# CM108B.net
KiCad netlist of a schematic drawn in Altium Designer
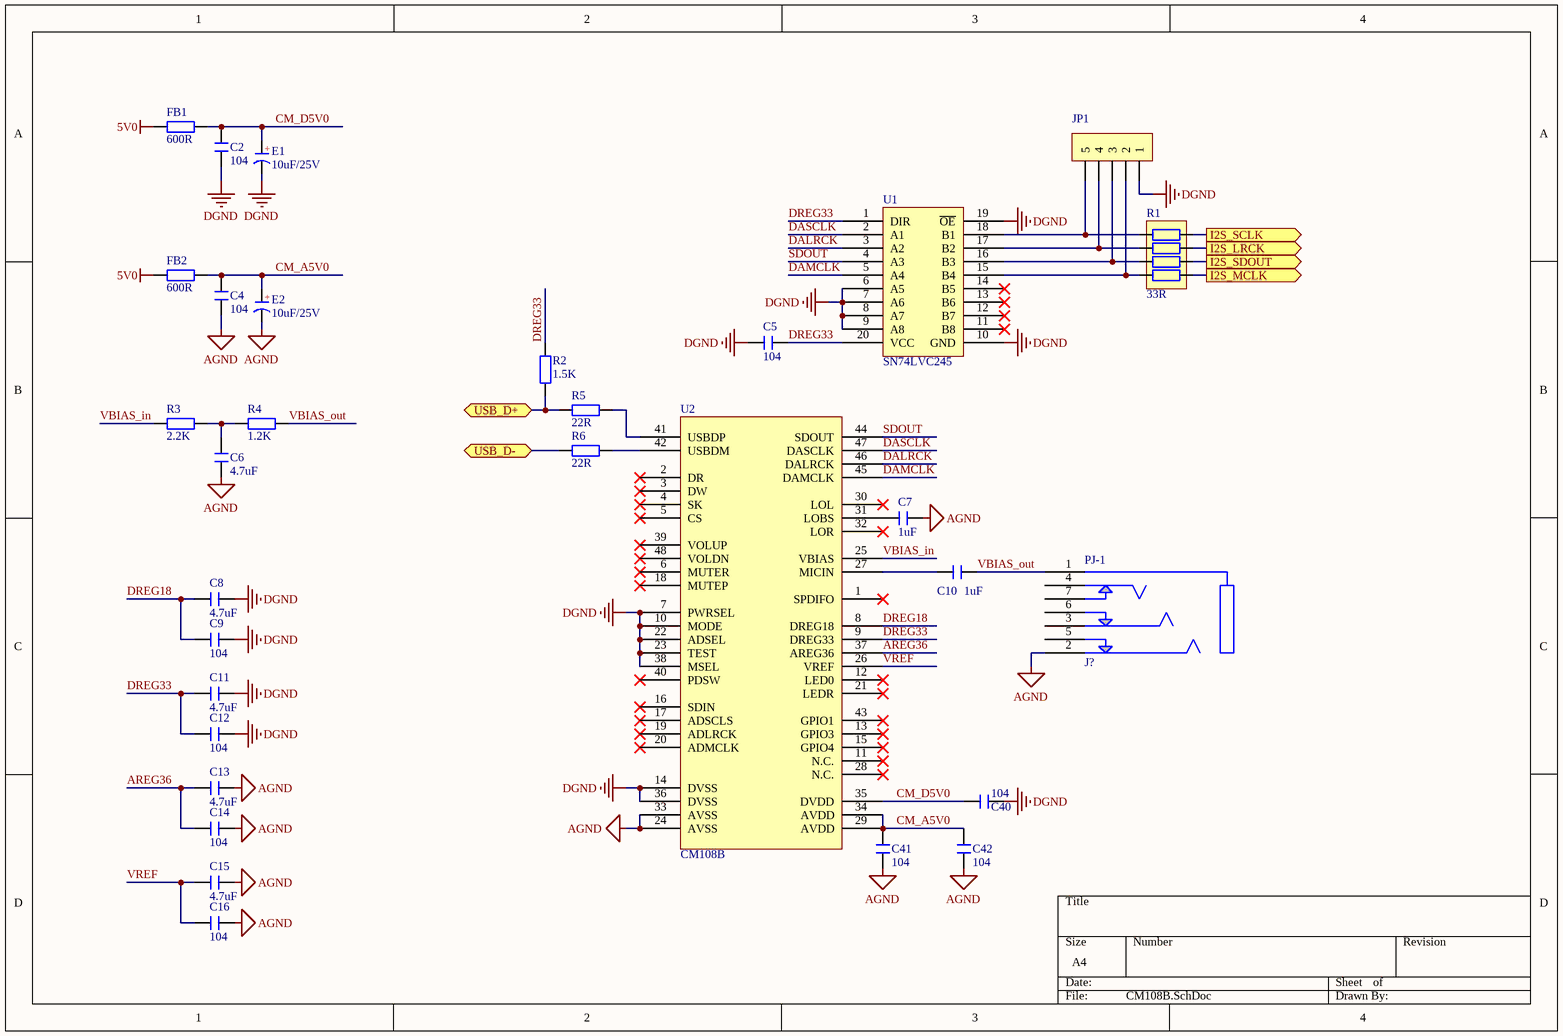
[diagram p0: CM108B.SchDoc]

(export (version "E")
  (design (tool "Eeschema 10.0.6"))
  (components
    (comp (ref "C2")
      (value "104")
      (footprint "C 0603_L")
      (description "贴片电容")
      (libsource (lib "0.1 - 电阻-电容-电感") (part "C"))
    )
    (comp (ref "C4")
      (value "104")
      (footprint "C 0603_L")
      (description "贴片电容")
      (libsource (lib "0.1 - 电阻-电容-电感") (part "C"))
    )
    (comp (ref "C5")
      (value "104")
      (footprint "C 0603_L")
      (description "贴片电容")
      (libsource (lib "0.1 - 电阻-电容-电感") (part "C"))
    )
    (comp (ref "C6")
      (value "4.7uF")
      (footprint "C 0603_L")
      (description "贴片电容")
      (libsource (lib "0.1 - 电阻-电容-电感") (part "C"))
    )
    (comp (ref "C7")
      (value "1uF")
      (footprint "C 0603_L")
      (description "贴片电容")
      (libsource (lib "0.1 - 电阻-电容-电感") (part "C"))
    )
    (comp (ref "C8")
      (value "4.7uF")
      (footprint "C 0603_L")
      (description "贴片电容")
      (libsource (lib "0.1 - 电阻-电容-电感") (part "C"))
    )
    (comp (ref "C9")
      (value "104")
      (footprint "C 0603_L")
      (description "贴片电容")
      (libsource (lib "0.1 - 电阻-电容-电感") (part "C"))
    )
    (comp (ref "C10")
      (value "1uF")
      (footprint "WIMA 1uF")
      (description "贴片电容")
      (libsource (lib "0.1 - 电阻-电容-电感") (part "C"))
    )
    (comp (ref "C11")
      (value "4.7uF")
      (footprint "C 0603_L")
      (description "贴片电容")
      (libsource (lib "0.1 - 电阻-电容-电感") (part "C"))
    )
    (comp (ref "C12")
      (value "104")
      (footprint "C 0603_L")
      (description "贴片电容")
      (libsource (lib "0.1 - 电阻-电容-电感") (part "C"))
    )
    (comp (ref "C13")
      (value "4.7uF")
      (footprint "C 0603_L")
      (description "贴片电容")
      (libsource (lib "0.1 - 电阻-电容-电感") (part "C"))
    )
    (comp (ref "C14")
      (value "104")
      (footprint "C 0603_L")
      (description "贴片电容")
      (libsource (lib "0.1 - 电阻-电容-电感") (part "C"))
    )
    (comp (ref "C15")
      (value "4.7uF")
      (footprint "C 0603_L")
      (description "贴片电容")
      (libsource (lib "0.1 - 电阻-电容-电感") (part "C"))
    )
    (comp (ref "C16")
      (value "104")
      (footprint "C 0603_L")
      (description "贴片电容")
      (libsource (lib "0.1 - 电阻-电容-电感") (part "C"))
    )
    (comp (ref "C40")
      (value "104")
      (footprint "C 0603_L")
      (description "贴片电容")
      (libsource (lib "0.1 - 电阻-电容-电感") (part "C"))
    )
    (comp (ref "C41")
      (value "104")
      (footprint "C 0603_L")
      (description "贴片电容")
      (libsource (lib "0.1 - 电阻-电容-电感") (part "C"))
    )
    (comp (ref "C42")
      (value "104")
      (footprint "C 0603_L")
      (description "贴片电容")
      (libsource (lib "0.1 - 电阻-电容-电感") (part "C"))
    )
    (comp (ref "E1")
      (value "10uF/25V")
      (footprint "CD A(3216)")
      (description "贴片钽电容")
      (libsource (lib "0.1 - 电阻-电容-电感") (part "CT"))
    )
    (comp (ref "E2")
      (value "10uF/25V")
      (footprint "CD A(3216)")
      (description "贴片钽电容")
      (libsource (lib "0.1 - 电阻-电容-电感") (part "CT"))
    )
    (comp (ref "FB1")
      (value "600R")
      (footprint "R 0805_L")
      (description "贴片电阻")
      (libsource (lib "0.1 - 电阻-电容-电感") (part "R"))
    )
    (comp (ref "FB2")
      (value "600R")
      (footprint "R 0805_L")
      (description "贴片电阻")
      (libsource (lib "0.1 - 电阻-电容-电感") (part "R"))
    )
    (comp (ref "JP1")
      (value "HDR-1X5")
      (footprint "HDR2.54-LI-5P")
      (description "5P接插件")
      (fields (field (name "版权归属") "封装库来自淘宝 ID：黄晶宝石"))
      (libsource (lib "5.4 - 接插件-脚距2.54 (100mil) ") (part "Header 5"))
    )
    (comp (ref "PJ-1")
      (value "J?")
      (footprint "PJ-393-7A")
      (description "3.5mm 4段 耳机插座")
      (libsource (lib "音频接口") (part "PJ-393-7"))
    )
    (comp (ref "R1")
      (value "33R")
      (footprint "RCA-8P4R-0402")
      (description "贴片排阻")
      (libsource (lib "0.1 - 电阻-电容-电感") (part "R-8P4R"))
    )
    (comp (ref "R2")
      (value "1.5K")
      (footprint "R 0603_L")
      (description "贴片电阻")
      (libsource (lib "0.1 - 电阻-电容-电感") (part "R"))
    )
    (comp (ref "R3")
      (value "2.2K")
      (footprint "R 0603_L")
      (description "贴片电阻")
      (libsource (lib "0.1 - 电阻-电容-电感") (part "R"))
    )
    (comp (ref "R4")
      (value "1.2K")
      (footprint "R 0603_L")
      (description "贴片电阻")
      (libsource (lib "0.1 - 电阻-电容-电感") (part "R"))
    )
    (comp (ref "R5")
      (value "22R")
      (footprint "R 0603_L")
      (description "贴片电阻")
      (libsource (lib "0.1 - 电阻-电容-电感") (part "R"))
    )
    (comp (ref "R6")
      (value "22R")
      (footprint "R 0603_L")
      (description "贴片电阻")
      (libsource (lib "0.1 - 电阻-电容-电感") (part "R"))
    )
    (comp (ref "U1")
      (value "SN74LVC245")
      (footprint "TSSOP20_N")
      (libsource (lib "1.4 - 74系列TTL芯片") (part "SN74LVC245"))
    )
    (comp (ref "U2")
      (value "CM108B")
      (footprint "LQFP48_N")
      (description "USB")
      (libsource (lib "音频芯片") (part "CM108B"))
    )
  )
  (nets
    (net (code "1") (name "/AREG36") (class "Default")
      (node (ref "C13") (pin "2") (pinfunction "2_2") (pintype "passive"))
      (node (ref "C14") (pin "1") (pinfunction "1_1") (pintype "passive"))
      (node (ref "U2") (pin "37") (pinfunction "AREG36_37") (pintype "passive"))
    )
    (net (code "2") (name "/CM_A5V0") (class "Default")
      (node (ref "C4") (pin "2") (pinfunction "2_2") (pintype "passive"))
      (node (ref "C41") (pin "1") (pinfunction "1_1") (pintype "passive"))
      (node (ref "C42") (pin "2") (pinfunction "2_2") (pintype "passive"))
      (node (ref "E2") (pin "1") (pinfunction "A_1") (pintype "passive"))
      (node (ref "FB2") (pin "2") (pinfunction "2_2") (pintype "passive"))
      (node (ref "U2") (pin "29") (pinfunction "AVDD_29") (pintype "passive"))
      (node (ref "U2") (pin "34") (pinfunction "AVDD_34") (pintype "passive"))
    )
    (net (code "3") (name "/CM_D5V0") (class "Default")
      (node (ref "C2") (pin "2") (pinfunction "2_2") (pintype "passive"))
      (node (ref "C40") (pin "1") (pinfunction "1_1") (pintype "passive"))
      (node (ref "E1") (pin "1") (pinfunction "A_1") (pintype "passive"))
      (node (ref "FB1") (pin "2") (pinfunction "2_2") (pintype "passive"))
      (node (ref "U2") (pin "35") (pinfunction "DVDD_35") (pintype "passive"))
    )
    (net (code "4") (name "/DALRCK") (class "Default")
      (node (ref "U1") (pin "3") (pinfunction "A2_3") (pintype "passive"))
      (node (ref "U2") (pin "46") (pinfunction "DALRCK_46") (pintype "passive"))
    )
    (net (code "5") (name "/DAMCLK") (class "Default")
      (node (ref "U1") (pin "5") (pinfunction "A4_5") (pintype "passive"))
      (node (ref "U2") (pin "45") (pinfunction "DAMCLK_45") (pintype "passive"))
    )
    (net (code "6") (name "/DASCLK") (class "Default")
      (node (ref "U1") (pin "2") (pinfunction "A1_2") (pintype "passive"))
      (node (ref "U2") (pin "47") (pinfunction "DASCLK_47") (pintype "passive"))
    )
    (net (code "7") (name "/DREG18") (class "Default")
      (node (ref "C8") (pin "2") (pinfunction "2_2") (pintype "passive"))
      (node (ref "C9") (pin "1") (pinfunction "1_1") (pintype "passive"))
      (node (ref "U2") (pin "8") (pinfunction "DREG18_8") (pintype "passive"))
    )
    (net (code "8") (name "/DREG33") (class "Default")
      (node (ref "C11") (pin "2") (pinfunction "2_2") (pintype "passive"))
      (node (ref "C12") (pin "1") (pinfunction "1_1") (pintype "passive"))
      (node (ref "C5") (pin "2") (pinfunction "2_2") (pintype "passive"))
      (node (ref "R2") (pin "2") (pinfunction "2_2") (pintype "passive"))
      (node (ref "U1") (pin "1") (pinfunction "DIR_1") (pintype "passive"))
      (node (ref "U1") (pin "20") (pinfunction "VCC_20") (pintype "passive"))
      (node (ref "U2") (pin "9") (pinfunction "DREG33_9") (pintype "passive"))
    )
    (net (code "9") (name "/I2S_LRCK") (class "Default")
      (node (ref "R1") (pin "3") (pinfunction "3_3") (pintype "passive"))
    )
    (net (code "10") (name "/I2S_MCLK") (class "Default")
      (node (ref "R1") (pin "1") (pinfunction "1_1") (pintype "passive"))
    )
    (net (code "11") (name "/I2S_SCLK") (class "Default")
      (node (ref "R1") (pin "4") (pinfunction "4_4") (pintype "passive"))
    )
    (net (code "12") (name "/I2S_SDOUT") (class "Default")
      (node (ref "R1") (pin "2") (pinfunction "2_2") (pintype "passive"))
    )
    (net (code "13") (name "/SDOUT") (class "Default")
      (node (ref "U1") (pin "4") (pinfunction "A3_4") (pintype "passive"))
      (node (ref "U2") (pin "44") (pinfunction "SDOUT_44") (pintype "passive"))
    )
    (net (code "14") (name "/USB_D+") (class "Default")
      (node (ref "R2") (pin "1") (pinfunction "1_1") (pintype "passive"))
      (node (ref "R5") (pin "1") (pinfunction "1_1") (pintype "passive"))
    )
    (net (code "15") (name "/USB_D-") (class "Default")
      (node (ref "R6") (pin "1") (pinfunction "1_1") (pintype "passive"))
    )
    (net (code "16") (name "/VBIAS_in") (class "Default")
      (node (ref "R3") (pin "1") (pinfunction "1_1") (pintype "passive"))
      (node (ref "U2") (pin "25") (pinfunction "VBIAS_25") (pintype "passive"))
    )
    (net (code "17") (name "/VBIAS_out") (class "Default")
      (node (ref "C10") (pin "2") (pinfunction "2_2") (pintype "passive"))
      (node (ref "PJ-1") (pin "1") (pinfunction "1_1") (pintype "passive"))
      (node (ref "R4") (pin "2") (pinfunction "2_2") (pintype "passive"))
    )
    (net (code "18") (name "/VREF") (class "Default")
      (node (ref "C15") (pin "2") (pinfunction "2_2") (pintype "passive"))
      (node (ref "C16") (pin "1") (pinfunction "1_1") (pintype "passive"))
      (node (ref "U2") (pin "26") (pinfunction "VREF_26") (pintype "passive"))
    )
    (net (code "19") (name "5V0") (class "Default")
      (node (ref "FB1") (pin "1") (pinfunction "1_1") (pintype "passive"))
      (node (ref "FB2") (pin "1") (pinfunction "1_1") (pintype "passive"))
    )
    (net (code "20") (name "AGND") (class "Default")
      (node (ref "C13") (pin "1") (pinfunction "1_1") (pintype "passive"))
      (node (ref "C14") (pin "2") (pinfunction "2_2") (pintype "passive"))
      (node (ref "C15") (pin "1") (pinfunction "1_1") (pintype "passive"))
      (node (ref "C16") (pin "2") (pinfunction "2_2") (pintype "passive"))
      (node (ref "C4") (pin "1") (pinfunction "1_1") (pintype "passive"))
      (node (ref "C41") (pin "2") (pinfunction "2_2") (pintype "passive"))
      (node (ref "C42") (pin "1") (pinfunction "1_1") (pintype "passive"))
      (node (ref "C6") (pin "2") (pinfunction "2_2") (pintype "passive"))
      (node (ref "C7") (pin "1") (pinfunction "1_1") (pintype "passive"))
      (node (ref "E2") (pin "2") (pinfunction "K_2") (pintype "passive"))
      (node (ref "PJ-1") (pin "2") (pinfunction "2_2") (pintype "passive"))
      (node (ref "U2") (pin "24") (pinfunction "AVSS_24") (pintype "passive"))
      (node (ref "U2") (pin "33") (pinfunction "AVSS_33") (pintype "passive"))
    )
    (net (code "21") (name "DGND") (class "Default")
      (node (ref "C11") (pin "1") (pinfunction "1_1") (pintype "passive"))
      (node (ref "C12") (pin "2") (pinfunction "2_2") (pintype "passive"))
      (node (ref "C2") (pin "1") (pinfunction "1_1") (pintype "passive"))
      (node (ref "C40") (pin "2") (pinfunction "2_2") (pintype "passive"))
      (node (ref "C5") (pin "1") (pinfunction "1_1") (pintype "passive"))
      (node (ref "C8") (pin "1") (pinfunction "1_1") (pintype "passive"))
      (node (ref "C9") (pin "2") (pinfunction "2_2") (pintype "passive"))
      (node (ref "E1") (pin "2") (pinfunction "K_2") (pintype "passive"))
      (node (ref "JP1") (pin "1") (pinfunction "1_1") (pintype "passive"))
      (node (ref "U1") (pin "10") (pinfunction "GND_10") (pintype "passive"))
      (node (ref "U1") (pin "19") (pinfunction "~{OE}_19") (pintype "passive"))
      (node (ref "U1") (pin "6") (pinfunction "A5_6") (pintype "passive"))
      (node (ref "U1") (pin "7") (pinfunction "A6_7") (pintype "passive"))
      (node (ref "U1") (pin "8") (pinfunction "A7_8") (pintype "passive"))
      (node (ref "U1") (pin "9") (pinfunction "A8_9") (pintype "passive"))
      (node (ref "U2") (pin "10") (pinfunction "MODE_10") (pintype "passive"))
      (node (ref "U2") (pin "14") (pinfunction "DVSS_14") (pintype "passive"))
      (node (ref "U2") (pin "22") (pinfunction "ADSEL_22") (pintype "passive"))
      (node (ref "U2") (pin "23") (pinfunction "TEST_23") (pintype "passive"))
      (node (ref "U2") (pin "36") (pinfunction "DVSS_36") (pintype "passive"))
      (node (ref "U2") (pin "38") (pinfunction "MSEL_38") (pintype "passive"))
      (node (ref "U2") (pin "7") (pinfunction "PWRSEL_7") (pintype "passive"))
    )
    (net (code "22") (name "Net-(C6-Pad1)") (class "Default")
      (node (ref "C6") (pin "1") (pinfunction "1_1") (pintype "passive"))
      (node (ref "R3") (pin "2") (pinfunction "2_2") (pintype "passive"))
      (node (ref "R4") (pin "1") (pinfunction "1_1") (pintype "passive"))
    )
    (net (code "23") (name "Net-(U1-B1)") (class "Default")
      (node (ref "JP1") (pin "5") (pinfunction "5_5") (pintype "passive"))
      (node (ref "R1") (pin "5") (pinfunction "5_5") (pintype "passive"))
      (node (ref "U1") (pin "18") (pinfunction "B1_18") (pintype "passive"))
    )
    (net (code "24") (name "Net-(U1-B2)") (class "Default")
      (node (ref "JP1") (pin "4") (pinfunction "4_4") (pintype "passive"))
      (node (ref "R1") (pin "6") (pinfunction "6_6") (pintype "passive"))
      (node (ref "U1") (pin "17") (pinfunction "B2_17") (pintype "passive"))
    )
    (net (code "25") (name "Net-(U1-B3)") (class "Default")
      (node (ref "JP1") (pin "3") (pinfunction "3_3") (pintype "passive"))
      (node (ref "R1") (pin "7") (pinfunction "7_7") (pintype "passive"))
      (node (ref "U1") (pin "16") (pinfunction "B3_16") (pintype "passive"))
    )
    (net (code "26") (name "Net-(U1-B4)") (class "Default")
      (node (ref "JP1") (pin "2") (pinfunction "2_2") (pintype "passive"))
      (node (ref "R1") (pin "8") (pinfunction "8_8") (pintype "passive"))
      (node (ref "U1") (pin "15") (pinfunction "B4_15") (pintype "passive"))
    )
    (net (code "27") (name "Net-(U2-LOBS)") (class "Default")
      (node (ref "C7") (pin "2") (pinfunction "2_2") (pintype "passive"))
      (node (ref "U2") (pin "31") (pinfunction "LOBS_31") (pintype "passive"))
    )
    (net (code "28") (name "Net-(U2-MICIN)") (class "Default")
      (node (ref "C10") (pin "1") (pinfunction "1_1") (pintype "passive"))
      (node (ref "U2") (pin "27") (pinfunction "MICIN_27") (pintype "passive"))
    )
    (net (code "29") (name "Net-(U2-USBDM)") (class "Default")
      (node (ref "R6") (pin "2") (pinfunction "2_2") (pintype "passive"))
      (node (ref "U2") (pin "42") (pinfunction "USBDM_42") (pintype "passive"))
    )
    (net (code "30") (name "Net-(U2-USBDP)") (class "Default")
      (node (ref "R5") (pin "2") (pinfunction "2_2") (pintype "passive"))
      (node (ref "U2") (pin "41") (pinfunction "USBDP_41") (pintype "passive"))
    )
    (net (code "31") (name "unconnected-(PJ-1-Pad3)") (class "Default")
      (node (ref "PJ-1") (pin "3") (pinfunction "3_3") (pintype "passive"))
    )
    (net (code "32") (name "unconnected-(PJ-1-Pad4)") (class "Default")
      (node (ref "PJ-1") (pin "4") (pinfunction "4_4") (pintype "passive"))
    )
    (net (code "33") (name "unconnected-(PJ-1-Pad5)") (class "Default")
      (node (ref "PJ-1") (pin "5") (pinfunction "5_5") (pintype "passive"))
    )
    (net (code "34") (name "unconnected-(PJ-1-Pad6)") (class "Default")
      (node (ref "PJ-1") (pin "6") (pinfunction "6_6") (pintype "passive"))
    )
    (net (code "35") (name "unconnected-(PJ-1-Pad7)") (class "Default")
      (node (ref "PJ-1") (pin "7") (pinfunction "7_7") (pintype "passive"))
    )
    (net (code "36") (name "unconnected-(U1-B5-Pad14)") (class "Default")
      (node (ref "U1") (pin "14") (pinfunction "B5_14") (pintype "passive+no_connect"))
    )
    (net (code "37") (name "unconnected-(U1-B6-Pad13)") (class "Default")
      (node (ref "U1") (pin "13") (pinfunction "B6_13") (pintype "passive+no_connect"))
    )
    (net (code "38") (name "unconnected-(U1-B7-Pad12)") (class "Default")
      (node (ref "U1") (pin "12") (pinfunction "B7_12") (pintype "passive+no_connect"))
    )
    (net (code "39") (name "unconnected-(U1-B8-Pad11)") (class "Default")
      (node (ref "U1") (pin "11") (pinfunction "B8_11") (pintype "passive+no_connect"))
    )
    (net (code "40") (name "unconnected-(U2-ADLRCK-Pad19)") (class "Default")
      (node (ref "U2") (pin "19") (pinfunction "ADLRCK_19") (pintype "passive+no_connect"))
    )
    (net (code "41") (name "unconnected-(U2-ADMCLK-Pad20)") (class "Default")
      (node (ref "U2") (pin "20") (pinfunction "ADMCLK_20") (pintype "passive+no_connect"))
    )
    (net (code "42") (name "unconnected-(U2-ADSCLS-Pad17)") (class "Default")
      (node (ref "U2") (pin "17") (pinfunction "ADSCLS_17") (pintype "passive+no_connect"))
    )
    (net (code "43") (name "unconnected-(U2-CS-Pad5)") (class "Default")
      (node (ref "U2") (pin "5") (pinfunction "CS_5") (pintype "passive+no_connect"))
    )
    (net (code "44") (name "unconnected-(U2-DR-Pad2)") (class "Default")
      (node (ref "U2") (pin "2") (pinfunction "DR_2") (pintype "passive+no_connect"))
    )
    (net (code "45") (name "unconnected-(U2-DW-Pad3)") (class "Default")
      (node (ref "U2") (pin "3") (pinfunction "DW_3") (pintype "passive+no_connect"))
    )
    (net (code "46") (name "unconnected-(U2-GPIO1-Pad43)") (class "Default")
      (node (ref "U2") (pin "43") (pinfunction "GPIO1_43") (pintype "passive+no_connect"))
    )
    (net (code "47") (name "unconnected-(U2-GPIO3-Pad13)") (class "Default")
      (node (ref "U2") (pin "13") (pinfunction "GPIO3_13") (pintype "passive+no_connect"))
    )
    (net (code "48") (name "unconnected-(U2-GPIO4-Pad15)") (class "Default")
      (node (ref "U2") (pin "15") (pinfunction "GPIO4_15") (pintype "passive+no_connect"))
    )
    (net (code "49") (name "unconnected-(U2-LED0-Pad12)") (class "Default")
      (node (ref "U2") (pin "12") (pinfunction "LED0_12") (pintype "passive+no_connect"))
    )
    (net (code "50") (name "unconnected-(U2-LEDR-Pad21)") (class "Default")
      (node (ref "U2") (pin "21") (pinfunction "LEDR_21") (pintype "passive+no_connect"))
    )
    (net (code "51") (name "unconnected-(U2-LOL-Pad30)") (class "Default")
      (node (ref "U2") (pin "30") (pinfunction "LOL_30") (pintype "passive+no_connect"))
    )
    (net (code "52") (name "unconnected-(U2-LOR-Pad32)") (class "Default")
      (node (ref "U2") (pin "32") (pinfunction "LOR_32") (pintype "passive+no_connect"))
    )
    (net (code "53") (name "unconnected-(U2-MUTEP-Pad18)") (class "Default")
      (node (ref "U2") (pin "18") (pinfunction "MUTEP_18") (pintype "passive+no_connect"))
    )
    (net (code "54") (name "unconnected-(U2-MUTER-Pad6)") (class "Default")
      (node (ref "U2") (pin "6") (pinfunction "MUTER_6") (pintype "passive+no_connect"))
    )
    (net (code "55") (name "unconnected-(U2-N.C.-Pad11)") (class "Default")
      (node (ref "U2") (pin "11") (pinfunction "N.C._11") (pintype "passive+no_connect"))
    )
    (net (code "56") (name "unconnected-(U2-N.C.-Pad28)") (class "Default")
      (node (ref "U2") (pin "28") (pinfunction "N.C._28") (pintype "passive+no_connect"))
    )
    (net (code "57") (name "unconnected-(U2-PDSW-Pad40)") (class "Default")
      (node (ref "U2") (pin "40") (pinfunction "PDSW_40") (pintype "passive+no_connect"))
    )
    (net (code "58") (name "unconnected-(U2-SDIN-Pad16)") (class "Default")
      (node (ref "U2") (pin "16") (pinfunction "SDIN_16") (pintype "passive+no_connect"))
    )
    (net (code "59") (name "unconnected-(U2-SK-Pad4)") (class "Default")
      (node (ref "U2") (pin "4") (pinfunction "SK_4") (pintype "passive+no_connect"))
    )
    (net (code "60") (name "unconnected-(U2-SPDIFO-Pad1)") (class "Default")
      (node (ref "U2") (pin "1") (pinfunction "SPDIFO_1") (pintype "passive+no_connect"))
    )
    (net (code "61") (name "unconnected-(U2-VOLDN-Pad48)") (class "Default")
      (node (ref "U2") (pin "48") (pinfunction "VOLDN_48") (pintype "passive+no_connect"))
    )
    (net (code "62") (name "unconnected-(U2-VOLUP-Pad39)") (class "Default")
      (node (ref "U2") (pin "39") (pinfunction "VOLUP_39") (pintype "passive+no_connect"))
    )
  )
)
